# AVR-BASE.net
KiCad netlist of a schematic drawn in EAGLE
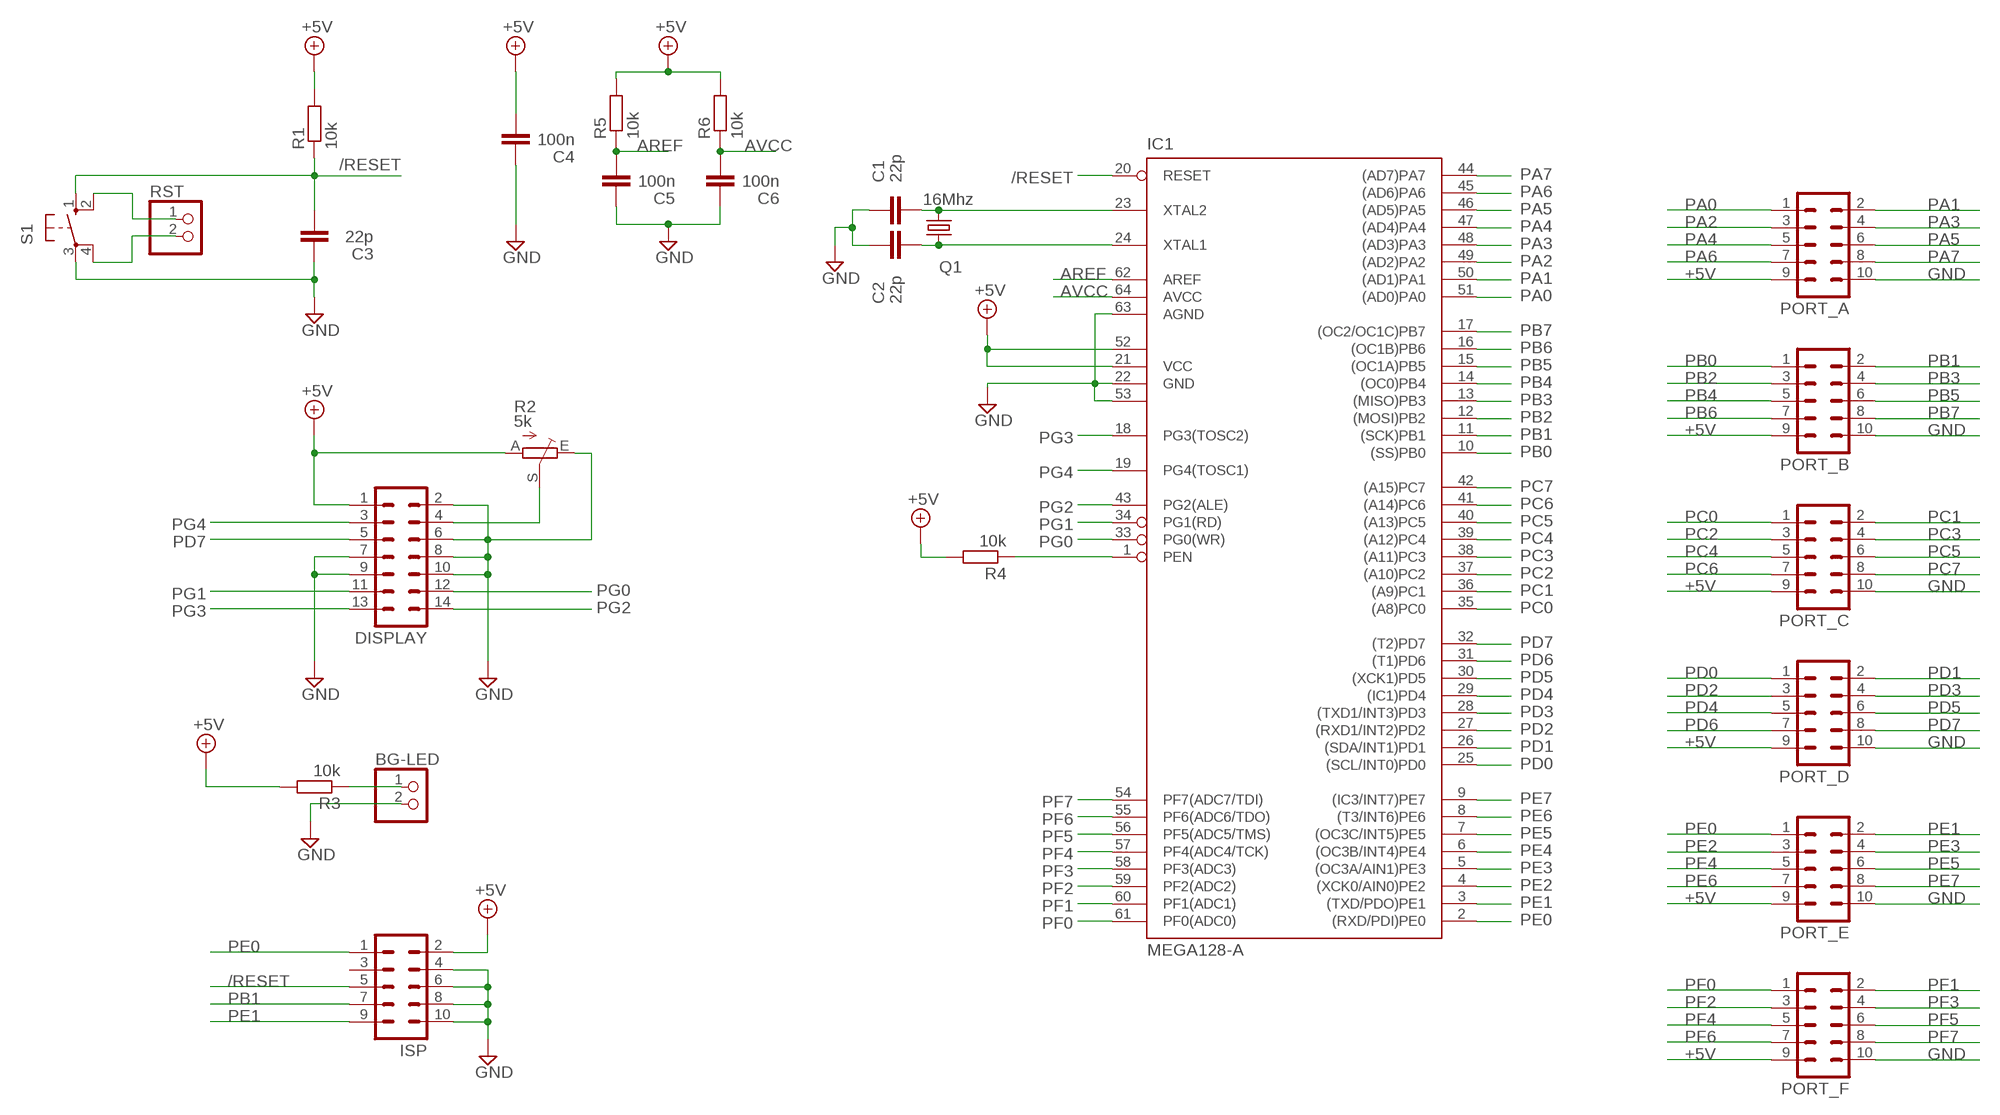
[diagram p0: schematic, sheet 1]
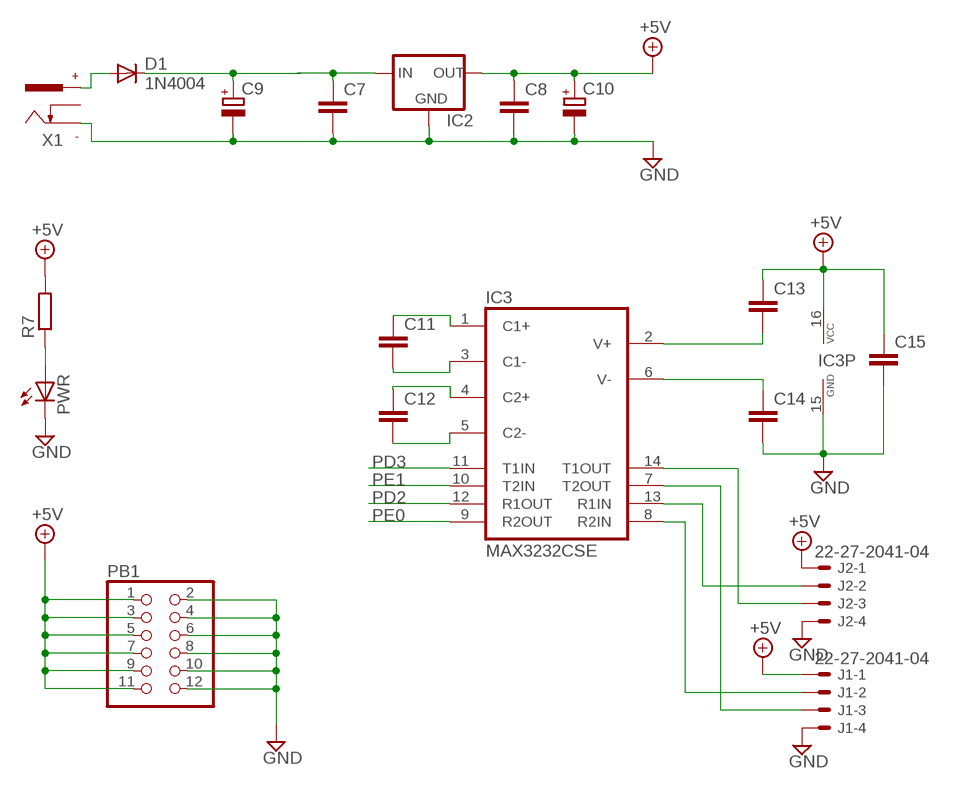
[diagram p1: schematic, sheet 2]

(export (version "E")
  (design (tool "Eeschema 10.0.6"))
  (components
    (comp (ref "C7")
      (value "C-EU025-025X050")
      (footprint "eagle-import:C025-025X050")
      (libsource (lib "eagle-import") (part "C-EU025-025X050"))
    )
    (comp (ref "C8")
      (value "C-EU025-025X050")
      (footprint "eagle-import:C025-025X050")
      (libsource (lib "eagle-import") (part "C-EU025-025X050"))
    )
    (comp (ref "C9")
      (value "CPOL-EUE3.5-8")
      (footprint "eagle-import:E3,5-8")
      (libsource (lib "eagle-import") (part "CPOL-EUE3.5-8"))
    )
    (comp (ref "C10")
      (value "CPOL-EUE3.5-8")
      (footprint "eagle-import:E3,5-8")
      (libsource (lib "eagle-import") (part "CPOL-EUE3.5-8"))
    )
    (comp (ref "C11")
      (value "C-EU025-025X050")
      (footprint "eagle-import:C025-025X050")
      (libsource (lib "eagle-import") (part "C-EU025-025X050"))
    )
    (comp (ref "C12")
      (value "C-EU025-025X050")
      (footprint "eagle-import:C025-025X050")
      (libsource (lib "eagle-import") (part "C-EU025-025X050"))
    )
    (comp (ref "C13")
      (value "C-EU025-025X050")
      (footprint "eagle-import:C025-025X050")
      (libsource (lib "eagle-import") (part "C-EU025-025X050"))
    )
    (comp (ref "C14")
      (value "C-EU025-025X050")
      (footprint "eagle-import:C025-025X050")
      (libsource (lib "eagle-import") (part "C-EU025-025X050"))
    )
    (comp (ref "C15")
      (value "C-EU025-025X050")
      (footprint "eagle-import:C025-025X050")
      (libsource (lib "eagle-import") (part "C-EU025-025X050"))
    )
    (comp (ref "D1")
      (value "1N4004")
      (footprint "eagle-import:DO41-10")
      (libsource (lib "eagle-import") (part "1N4004"))
    )
    (comp (ref "IC2")
      (value "78XXL")
      (footprint "eagle-import:78XXL")
      (libsource (lib "eagle-import") (part "78XXL"))
    )
    (comp (ref "IC3")
      (value "MAX3232CSE")
      (footprint "eagle-import:SO16")
      (libsource (lib "eagle-import") (part "MAX3232SEC"))
    )
    (comp (ref "J1")
      (value "22-27-2041-04")
      (footprint "eagle-import:6410-04")
      (libsource (lib "eagle-import") (part "22-?-0427-2041"))
    )
    (comp (ref "J2")
      (value "22-27-2041-04")
      (footprint "eagle-import:6410-04")
      (libsource (lib "eagle-import") (part "22-?-0427-2041"))
    )
    (comp (ref "PB1")
      (value "PINHD-2X6")
      (footprint "eagle-import:2X06")
      (libsource (lib "eagle-import") (part "PINHD-2X6"))
    )
    (comp (ref "PWR")
      (value "LED3MM")
      (footprint "eagle-import:LED3MM")
      (libsource (lib "eagle-import") (part "LED3MM"))
    )
    (comp (ref "R7")
      (value "R-EU_0204/5")
      (footprint "eagle-import:0204_5")
      (libsource (lib "eagle-import") (part "R-EU_0204/5"))
    )
    (comp (ref "X1")
      (value "737992-55")
      (footprint "eagle-import:737992-5")
      (libsource (lib "eagle-import") (part "737992-55"))
    )
    (comp (ref "BG-LED")
      (value "PINHD-1X2")
      (footprint "eagle-import:1X02")
      (libsource (lib "eagle-import") (part "PINHD-1X2"))
    )
    (comp (ref "C1")
      (value "22p")
      (footprint "eagle-import:C025-025X050")
      (libsource (lib "eagle-import") (part "C-EU025-025X050"))
    )
    (comp (ref "C2")
      (value "22p")
      (footprint "eagle-import:C025-025X050")
      (libsource (lib "eagle-import") (part "C-EU025-025X050"))
    )
    (comp (ref "C3")
      (value "22p")
      (footprint "eagle-import:C025-025X050")
      (libsource (lib "eagle-import") (part "C-EU025-025X050"))
    )
    (comp (ref "C4")
      (value "100n")
      (footprint "eagle-import:C025-025X050")
      (libsource (lib "eagle-import") (part "C-EU025-025X050"))
    )
    (comp (ref "C5")
      (value "100n")
      (footprint "eagle-import:C025-025X050")
      (libsource (lib "eagle-import") (part "C-EU025-025X050"))
    )
    (comp (ref "C6")
      (value "100n")
      (footprint "eagle-import:C025-025X050")
      (libsource (lib "eagle-import") (part "C-EU025-025X050"))
    )
    (comp (ref "DISPLAY")
      (value "ML14")
      (footprint "eagle-import:ML14")
      (libsource (lib "eagle-import") (part "ML14"))
    )
    (comp (ref "IC1")
      (value "MEGA128-A")
      (footprint "eagle-import:TQFP64")
      (libsource (lib "eagle-import") (part "MEGA128-A"))
    )
    (comp (ref "ISP")
      (value "ML10")
      (footprint "eagle-import:ML10")
      (libsource (lib "eagle-import") (part "ML10"))
    )
    (comp (ref "PORT_A")
      (value "ML10")
      (footprint "eagle-import:ML10")
      (libsource (lib "eagle-import") (part "ML10"))
    )
    (comp (ref "PORT_B")
      (value "ML10")
      (footprint "eagle-import:ML10")
      (libsource (lib "eagle-import") (part "ML10"))
    )
    (comp (ref "PORT_C")
      (value "ML10")
      (footprint "eagle-import:ML10")
      (libsource (lib "eagle-import") (part "ML10"))
    )
    (comp (ref "PORT_D")
      (value "ML10")
      (footprint "eagle-import:ML10")
      (libsource (lib "eagle-import") (part "ML10"))
    )
    (comp (ref "PORT_E")
      (value "ML10")
      (footprint "eagle-import:ML10")
      (libsource (lib "eagle-import") (part "ML10"))
    )
    (comp (ref "PORT_F")
      (value "ML10")
      (footprint "eagle-import:ML10")
      (libsource (lib "eagle-import") (part "ML10"))
    )
    (comp (ref "Q1")
      (value "16Mhz")
      (footprint "eagle-import:HC49U-V")
      (libsource (lib "eagle-import") (part "CRYSTALHC49U-V"))
    )
    (comp (ref "R1")
      (value "10k")
      (footprint "eagle-import:0207_7")
      (libsource (lib "eagle-import") (part "R-EU_0207/7"))
    )
    (comp (ref "R2")
      (value "5k")
      (footprint "eagle-import:B25P")
      (libsource (lib "eagle-import") (part "TRIM_EU-B25P"))
    )
    (comp (ref "R3")
      (value "10k")
      (footprint "eagle-import:0207_7")
      (libsource (lib "eagle-import") (part "R-EU_0207/7"))
    )
    (comp (ref "R4")
      (value "10k")
      (footprint "eagle-import:0204_5")
      (libsource (lib "eagle-import") (part "R-EU_0204/5"))
    )
    (comp (ref "R5")
      (value "10k")
      (footprint "eagle-import:0204_5")
      (libsource (lib "eagle-import") (part "R-EU_0204/5"))
    )
    (comp (ref "R6")
      (value "10k")
      (footprint "eagle-import:0204_5")
      (libsource (lib "eagle-import") (part "R-EU_0204/5"))
    )
    (comp (ref "RST")
      (value "PINHD-1X2")
      (footprint "eagle-import:1X02")
      (libsource (lib "eagle-import") (part "PINHD-1X2"))
    )
    (comp (ref "S1")
      (value "10-XX")
      (footprint "eagle-import:B3F-10XX")
      (libsource (lib "eagle-import") (part "10-XX"))
    )
  )
  (nets
    (net (code "1") (name "+5V") (class "Default")
      (node (ref "C10") (pin "+") (pinfunction "+_+") (pintype "passive"))
      (node (ref "C13") (pin "1") (pinfunction "1_1") (pintype "passive"))
      (node (ref "C15") (pin "1") (pinfunction "1_1") (pintype "passive"))
      (node (ref "C4") (pin "2") (pinfunction "2_2") (pintype "passive"))
      (node (ref "C8") (pin "1") (pinfunction "1_1") (pintype "passive"))
      (node (ref "DISPLAY") (pin "1") (pinfunction "1_1") (pintype "passive"))
      (node (ref "IC1") (pin "21") (pinfunction "VCC_21") (pintype "power_in"))
      (node (ref "IC1") (pin "52") (pinfunction "VCC1_52") (pintype "power_in"))
      (node (ref "IC2") (pin "OUT") (pinfunction "OUT_OUT") (pintype "passive"))
      (node (ref "IC3") (pin "16") (pinfunction "VCC_16") (pintype "power_in"))
      (node (ref "ISP") (pin "2") (pinfunction "2_2") (pintype "passive"))
      (node (ref "J1") (pin "1") (pinfunction "S_1") (pintype "passive"))
      (node (ref "J2") (pin "1") (pinfunction "S_1") (pintype "passive"))
      (node (ref "PB1") (pin "1") (pinfunction "1_1") (pintype "passive"))
      (node (ref "PB1") (pin "11") (pinfunction "11_11") (pintype "passive"))
      (node (ref "PB1") (pin "3") (pinfunction "3_3") (pintype "passive"))
      (node (ref "PB1") (pin "5") (pinfunction "5_5") (pintype "passive"))
      (node (ref "PB1") (pin "7") (pinfunction "7_7") (pintype "passive"))
      (node (ref "PB1") (pin "9") (pinfunction "9_9") (pintype "passive"))
      (node (ref "PORT_A") (pin "9") (pinfunction "9_9") (pintype "passive"))
      (node (ref "PORT_B") (pin "9") (pinfunction "9_9") (pintype "passive"))
      (node (ref "PORT_C") (pin "9") (pinfunction "9_9") (pintype "passive"))
      (node (ref "PORT_D") (pin "9") (pinfunction "9_9") (pintype "passive"))
      (node (ref "PORT_E") (pin "9") (pinfunction "9_9") (pintype "passive"))
      (node (ref "PORT_F") (pin "9") (pinfunction "9_9") (pintype "passive"))
      (node (ref "R1") (pin "2") (pinfunction "2_2") (pintype "passive"))
      (node (ref "R2") (pin "A") (pinfunction "A_A") (pintype "passive"))
      (node (ref "R3") (pin "2") (pinfunction "2_2") (pintype "passive"))
      (node (ref "R4") (pin "2") (pinfunction "2_2") (pintype "passive"))
      (node (ref "R5") (pin "2") (pinfunction "2_2") (pintype "passive"))
      (node (ref "R6") (pin "2") (pinfunction "2_2") (pintype "passive"))
      (node (ref "R7") (pin "2") (pinfunction "2_2") (pintype "passive"))
    )
    (net (code "2") (name "AREF") (class "Default")
      (node (ref "C5") (pin "2") (pinfunction "2_2") (pintype "passive"))
      (node (ref "IC1") (pin "62") (pinfunction "AREF_62") (pintype "bidirectional"))
      (node (ref "R5") (pin "1") (pinfunction "1_1") (pintype "passive"))
    )
    (net (code "3") (name "AVCC") (class "Default")
      (node (ref "C6") (pin "2") (pinfunction "2_2") (pintype "passive"))
      (node (ref "IC1") (pin "64") (pinfunction "AVCC_64") (pintype "bidirectional"))
      (node (ref "R6") (pin "1") (pinfunction "1_1") (pintype "passive"))
    )
    (net (code "4") (name "GND") (class "Default")
      (node (ref "BG-LED") (pin "2") (pinfunction "2_2") (pintype "passive"))
      (node (ref "C1") (pin "1") (pinfunction "1_1") (pintype "passive"))
      (node (ref "C10") (pin "-") (pinfunction "-_-") (pintype "passive"))
      (node (ref "C14") (pin "2") (pinfunction "2_2") (pintype "passive"))
      (node (ref "C15") (pin "2") (pinfunction "2_2") (pintype "passive"))
      (node (ref "C2") (pin "1") (pinfunction "1_1") (pintype "passive"))
      (node (ref "C3") (pin "1") (pinfunction "1_1") (pintype "passive"))
      (node (ref "C4") (pin "1") (pinfunction "1_1") (pintype "passive"))
      (node (ref "C5") (pin "1") (pinfunction "1_1") (pintype "passive"))
      (node (ref "C6") (pin "1") (pinfunction "1_1") (pintype "passive"))
      (node (ref "C7") (pin "2") (pinfunction "2_2") (pintype "passive"))
      (node (ref "C8") (pin "2") (pinfunction "2_2") (pintype "passive"))
      (node (ref "C9") (pin "-") (pinfunction "-_-") (pintype "passive"))
      (node (ref "DISPLAY") (pin "10") (pinfunction "10_10") (pintype "passive"))
      (node (ref "DISPLAY") (pin "2") (pinfunction "2_2") (pintype "passive"))
      (node (ref "DISPLAY") (pin "6") (pinfunction "6_6") (pintype "passive"))
      (node (ref "DISPLAY") (pin "7") (pinfunction "7_7") (pintype "passive"))
      (node (ref "DISPLAY") (pin "8") (pinfunction "8_8") (pintype "passive"))
      (node (ref "DISPLAY") (pin "9") (pinfunction "9_9") (pintype "passive"))
      (node (ref "IC1") (pin "22") (pinfunction "GND_22") (pintype "power_in"))
      (node (ref "IC1") (pin "53") (pinfunction "GND1_53") (pintype "power_in"))
      (node (ref "IC1") (pin "63") (pinfunction "AGND_63") (pintype "bidirectional"))
      (node (ref "IC2") (pin "GND") (pinfunction "GND_GND") (pintype "input"))
      (node (ref "IC3") (pin "15") (pinfunction "GND_15") (pintype "power_in"))
      (node (ref "ISP") (pin "10") (pinfunction "10_10") (pintype "passive"))
      (node (ref "ISP") (pin "4") (pinfunction "4_4") (pintype "passive"))
      (node (ref "ISP") (pin "6") (pinfunction "6_6") (pintype "passive"))
      (node (ref "ISP") (pin "8") (pinfunction "8_8") (pintype "passive"))
      (node (ref "J1") (pin "4") (pinfunction "S_4") (pintype "passive"))
      (node (ref "J2") (pin "4") (pinfunction "S_4") (pintype "passive"))
      (node (ref "PB1") (pin "10") (pinfunction "10_10") (pintype "passive"))
      (node (ref "PB1") (pin "12") (pinfunction "12_12") (pintype "passive"))
      (node (ref "PB1") (pin "2") (pinfunction "2_2") (pintype "passive"))
      (node (ref "PB1") (pin "4") (pinfunction "4_4") (pintype "passive"))
      (node (ref "PB1") (pin "6") (pinfunction "6_6") (pintype "passive"))
      (node (ref "PB1") (pin "8") (pinfunction "8_8") (pintype "passive"))
      (node (ref "PORT_A") (pin "10") (pinfunction "10_10") (pintype "passive"))
      (node (ref "PORT_B") (pin "10") (pinfunction "10_10") (pintype "passive"))
      (node (ref "PORT_C") (pin "10") (pinfunction "10_10") (pintype "passive"))
      (node (ref "PORT_D") (pin "10") (pinfunction "10_10") (pintype "passive"))
      (node (ref "PORT_E") (pin "10") (pinfunction "10_10") (pintype "passive"))
      (node (ref "PORT_F") (pin "10") (pinfunction "10_10") (pintype "passive"))
      (node (ref "PWR") (pin "K") (pinfunction "C_K") (pintype "passive"))
      (node (ref "R2") (pin "E") (pinfunction "E_E") (pintype "passive"))
      (node (ref "S1") (pin "3") (pinfunction "P_3") (pintype "passive"))
      (node (ref "X1") (pin "+") (pinfunction "+_+") (pintype "passive"))
    )
    (net (code "5") (name "Net-(BG-LED-Pad1)") (class "Default")
      (node (ref "BG-LED") (pin "1") (pinfunction "1_1") (pintype "passive"))
      (node (ref "R3") (pin "1") (pinfunction "1_1") (pintype "passive"))
    )
    (net (code "6") (name "Net-(C7-Pad1)") (class "Default")
      (node (ref "C7") (pin "1") (pinfunction "1_1") (pintype "passive"))
      (node (ref "C9") (pin "+") (pinfunction "+_+") (pintype "passive"))
      (node (ref "D1") (pin "C") (pinfunction "C_C") (pintype "passive"))
      (node (ref "IC2") (pin "IN") (pinfunction "IN_IN") (pintype "input"))
    )
    (net (code "7") (name "Net-(D1-PadA)") (class "Default")
      (node (ref "D1") (pin "A") (pinfunction "A_A") (pintype "passive"))
      (node (ref "X1") (pin "-1") (pinfunction "-1_-1") (pintype "passive"))
    )
    (net (code "8") (name "Net-(DISPLAY-Pad4)") (class "Default")
      (node (ref "DISPLAY") (pin "4") (pinfunction "4_4") (pintype "passive"))
      (node (ref "R2") (pin "S") (pinfunction "S_S") (pintype "passive"))
    )
    (net (code "9") (name "Net-(IC1-PEN)") (class "Default")
      (node (ref "IC1") (pin "1") (pinfunction "PEN_1") (pintype "input"))
      (node (ref "R4") (pin "1") (pinfunction "1_1") (pintype "passive"))
    )
    (net (code "10") (name "Net-(IC1-XTAL1)") (class "Default")
      (node (ref "C2") (pin "2") (pinfunction "2_2") (pintype "passive"))
      (node (ref "IC1") (pin "24") (pinfunction "XTAL1_24") (pintype "bidirectional"))
      (node (ref "Q1") (pin "1") (pinfunction "1_1") (pintype "passive"))
    )
    (net (code "11") (name "Net-(IC1-XTAL2)") (class "Default")
      (node (ref "C1") (pin "2") (pinfunction "2_2") (pintype "passive"))
      (node (ref "IC1") (pin "23") (pinfunction "XTAL2_23") (pintype "bidirectional"))
      (node (ref "Q1") (pin "2") (pinfunction "2_2") (pintype "passive"))
    )
    (net (code "12") (name "Net-(IC3A-C1+)") (class "Default")
      (node (ref "C11") (pin "1") (pinfunction "1_1") (pintype "passive"))
      (node (ref "IC3") (pin "1") (pinfunction "C1+_1") (pintype "bidirectional"))
    )
    (net (code "13") (name "Net-(IC3A-C1-)") (class "Default")
      (node (ref "C11") (pin "2") (pinfunction "2_2") (pintype "passive"))
      (node (ref "IC3") (pin "3") (pinfunction "C1-_3") (pintype "bidirectional"))
    )
    (net (code "14") (name "Net-(IC3A-C2+)") (class "Default")
      (node (ref "C12") (pin "1") (pinfunction "1_1") (pintype "passive"))
      (node (ref "IC3") (pin "4") (pinfunction "C2+_4") (pintype "bidirectional"))
    )
    (net (code "15") (name "Net-(IC3A-C2-)") (class "Default")
      (node (ref "C12") (pin "2") (pinfunction "2_2") (pintype "passive"))
      (node (ref "IC3") (pin "5") (pinfunction "C2-_5") (pintype "bidirectional"))
    )
    (net (code "16") (name "Net-(IC3A-R1IN)") (class "Default")
      (node (ref "IC3") (pin "13") (pinfunction "R1IN_13") (pintype "input"))
      (node (ref "J2") (pin "2") (pinfunction "S_2") (pintype "passive"))
    )
    (net (code "17") (name "Net-(IC3A-R2IN)") (class "Default")
      (node (ref "IC3") (pin "8") (pinfunction "R2IN_8") (pintype "input"))
      (node (ref "J1") (pin "2") (pinfunction "S_2") (pintype "passive"))
    )
    (net (code "18") (name "Net-(IC3A-T1OUT)") (class "Default")
      (node (ref "IC3") (pin "14") (pinfunction "T1OUT_14") (pintype "output"))
      (node (ref "J2") (pin "3") (pinfunction "S_3") (pintype "passive"))
    )
    (net (code "19") (name "Net-(IC3A-T2OUT)") (class "Default")
      (node (ref "IC3") (pin "7") (pinfunction "T2OUT_7") (pintype "output"))
      (node (ref "J1") (pin "3") (pinfunction "S_3") (pintype "passive"))
    )
    (net (code "20") (name "Net-(IC3A-V+)") (class "Default")
      (node (ref "C13") (pin "2") (pinfunction "2_2") (pintype "passive"))
      (node (ref "IC3") (pin "2") (pinfunction "V+_2") (pintype "bidirectional"))
    )
    (net (code "21") (name "Net-(IC3A-V-)") (class "Default")
      (node (ref "C14") (pin "1") (pinfunction "1_1") (pintype "passive"))
      (node (ref "IC3") (pin "6") (pinfunction "V-_6") (pintype "bidirectional"))
    )
    (net (code "22") (name "Net-(PWR-PadA)") (class "Default")
      (node (ref "PWR") (pin "A") (pinfunction "A_A") (pintype "passive"))
      (node (ref "R7") (pin "1") (pinfunction "1_1") (pintype "passive"))
    )
    (net (code "23") (name "Net-(S1-P1)") (class "Default")
      (node (ref "RST") (pin "2") (pinfunction "2_2") (pintype "passive"))
      (node (ref "S1") (pin "4") (pinfunction "P1_4") (pintype "passive"))
    )
    (net (code "24") (name "Net-(S1-S1)") (class "Default")
      (node (ref "RST") (pin "1") (pinfunction "1_1") (pintype "passive"))
      (node (ref "S1") (pin "2") (pinfunction "S1_2") (pintype "passive"))
    )
    (net (code "25") (name "PA0") (class "Default")
      (node (ref "IC1") (pin "51") (pinfunction "(AD0)PA0_51") (pintype "bidirectional"))
      (node (ref "PORT_A") (pin "1") (pinfunction "1_1") (pintype "passive"))
    )
    (net (code "26") (name "PA1") (class "Default")
      (node (ref "IC1") (pin "50") (pinfunction "(AD1)PA1_50") (pintype "bidirectional"))
      (node (ref "PORT_A") (pin "2") (pinfunction "2_2") (pintype "passive"))
    )
    (net (code "27") (name "PA2") (class "Default")
      (node (ref "IC1") (pin "49") (pinfunction "(AD2)PA2_49") (pintype "bidirectional"))
      (node (ref "PORT_A") (pin "3") (pinfunction "3_3") (pintype "passive"))
    )
    (net (code "28") (name "PA3") (class "Default")
      (node (ref "IC1") (pin "48") (pinfunction "(AD3)PA3_48") (pintype "bidirectional"))
      (node (ref "PORT_A") (pin "4") (pinfunction "4_4") (pintype "passive"))
    )
    (net (code "29") (name "PA4") (class "Default")
      (node (ref "IC1") (pin "47") (pinfunction "(AD4)PA4_47") (pintype "bidirectional"))
      (node (ref "PORT_A") (pin "5") (pinfunction "5_5") (pintype "passive"))
    )
    (net (code "30") (name "PA5") (class "Default")
      (node (ref "IC1") (pin "46") (pinfunction "(AD5)PA5_46") (pintype "bidirectional"))
      (node (ref "PORT_A") (pin "6") (pinfunction "6_6") (pintype "passive"))
    )
    (net (code "31") (name "PA6") (class "Default")
      (node (ref "IC1") (pin "45") (pinfunction "(AD6)PA6_45") (pintype "bidirectional"))
      (node (ref "PORT_A") (pin "7") (pinfunction "7_7") (pintype "passive"))
    )
    (net (code "32") (name "PA7") (class "Default")
      (node (ref "IC1") (pin "44") (pinfunction "(AD7)PA7_44") (pintype "bidirectional"))
      (node (ref "PORT_A") (pin "8") (pinfunction "8_8") (pintype "passive"))
    )
    (net (code "33") (name "PB0") (class "Default")
      (node (ref "IC1") (pin "10") (pinfunction "(SS)PB0_10") (pintype "bidirectional"))
      (node (ref "PORT_B") (pin "1") (pinfunction "1_1") (pintype "passive"))
    )
    (net (code "34") (name "PB1") (class "Default")
      (node (ref "IC1") (pin "11") (pinfunction "(SCK)PB1_11") (pintype "bidirectional"))
      (node (ref "ISP") (pin "7") (pinfunction "7_7") (pintype "passive"))
      (node (ref "PORT_B") (pin "2") (pinfunction "2_2") (pintype "passive"))
    )
    (net (code "35") (name "PB2") (class "Default")
      (node (ref "IC1") (pin "12") (pinfunction "(MOSI)PB2_12") (pintype "bidirectional"))
      (node (ref "PORT_B") (pin "3") (pinfunction "3_3") (pintype "passive"))
    )
    (net (code "36") (name "PB3") (class "Default")
      (node (ref "IC1") (pin "13") (pinfunction "(MISO)PB3_13") (pintype "bidirectional"))
      (node (ref "PORT_B") (pin "4") (pinfunction "4_4") (pintype "passive"))
    )
    (net (code "37") (name "PB4") (class "Default")
      (node (ref "IC1") (pin "14") (pinfunction "(OC0)PB4_14") (pintype "bidirectional"))
      (node (ref "PORT_B") (pin "5") (pinfunction "5_5") (pintype "passive"))
    )
    (net (code "38") (name "PB5") (class "Default")
      (node (ref "IC1") (pin "15") (pinfunction "(OC1A)PB5_15") (pintype "bidirectional"))
      (node (ref "PORT_B") (pin "6") (pinfunction "6_6") (pintype "passive"))
    )
    (net (code "39") (name "PB6") (class "Default")
      (node (ref "IC1") (pin "16") (pinfunction "(OC1B)PB6_16") (pintype "bidirectional"))
      (node (ref "PORT_B") (pin "7") (pinfunction "7_7") (pintype "passive"))
    )
    (net (code "40") (name "PB7") (class "Default")
      (node (ref "IC1") (pin "17") (pinfunction "(OC2/OC1C)PB7_17") (pintype "bidirectional"))
      (node (ref "PORT_B") (pin "8") (pinfunction "8_8") (pintype "passive"))
    )
    (net (code "41") (name "PC0") (class "Default")
      (node (ref "IC1") (pin "35") (pinfunction "(A8)PC0_35") (pintype "output"))
      (node (ref "PORT_C") (pin "1") (pinfunction "1_1") (pintype "passive"))
    )
    (net (code "42") (name "PC1") (class "Default")
      (node (ref "IC1") (pin "36") (pinfunction "(A9)PC1_36") (pintype "output"))
      (node (ref "PORT_C") (pin "2") (pinfunction "2_2") (pintype "passive"))
    )
    (net (code "43") (name "PC2") (class "Default")
      (node (ref "IC1") (pin "37") (pinfunction "(A10)PC2_37") (pintype "output"))
      (node (ref "PORT_C") (pin "3") (pinfunction "3_3") (pintype "passive"))
    )
    (net (code "44") (name "PC3") (class "Default")
      (node (ref "IC1") (pin "38") (pinfunction "(A11)PC3_38") (pintype "output"))
      (node (ref "PORT_C") (pin "4") (pinfunction "4_4") (pintype "passive"))
    )
    (net (code "45") (name "PC4") (class "Default")
      (node (ref "IC1") (pin "39") (pinfunction "(A12)PC4_39") (pintype "output"))
      (node (ref "PORT_C") (pin "5") (pinfunction "5_5") (pintype "passive"))
    )
    (net (code "46") (name "PC5") (class "Default")
      (node (ref "IC1") (pin "40") (pinfunction "(A13)PC5_40") (pintype "output"))
      (node (ref "PORT_C") (pin "6") (pinfunction "6_6") (pintype "passive"))
    )
    (net (code "47") (name "PC6") (class "Default")
      (node (ref "IC1") (pin "41") (pinfunction "(A14)PC6_41") (pintype "output"))
      (node (ref "PORT_C") (pin "7") (pinfunction "7_7") (pintype "passive"))
    )
    (net (code "48") (name "PC7") (class "Default")
      (node (ref "IC1") (pin "42") (pinfunction "(A15)PC7_42") (pintype "output"))
      (node (ref "PORT_C") (pin "8") (pinfunction "8_8") (pintype "passive"))
    )
    (net (code "49") (name "PD0") (class "Default")
      (node (ref "IC1") (pin "25") (pinfunction "(SCL/INT0)PD0_25") (pintype "bidirectional"))
      (node (ref "PORT_D") (pin "1") (pinfunction "1_1") (pintype "passive"))
    )
    (net (code "50") (name "PD1") (class "Default")
      (node (ref "IC1") (pin "26") (pinfunction "(SDA/INT1)PD1_26") (pintype "bidirectional"))
      (node (ref "PORT_D") (pin "2") (pinfunction "2_2") (pintype "passive"))
    )
    (net (code "51") (name "PD2") (class "Default")
      (node (ref "IC1") (pin "27") (pinfunction "(RXD1/INT2)PD2_27") (pintype "bidirectional"))
      (node (ref "IC3") (pin "12") (pinfunction "R1OUT_12") (pintype "output"))
      (node (ref "PORT_D") (pin "3") (pinfunction "3_3") (pintype "passive"))
    )
    (net (code "52") (name "PD3") (class "Default")
      (node (ref "IC1") (pin "28") (pinfunction "(TXD1/INT3)PD3_28") (pintype "bidirectional"))
      (node (ref "IC3") (pin "11") (pinfunction "T1IN_11") (pintype "input"))
      (node (ref "PORT_D") (pin "4") (pinfunction "4_4") (pintype "passive"))
    )
    (net (code "53") (name "PD4") (class "Default")
      (node (ref "IC1") (pin "29") (pinfunction "(IC1)PD4_29") (pintype "bidirectional"))
      (node (ref "PORT_D") (pin "5") (pinfunction "5_5") (pintype "passive"))
    )
    (net (code "54") (name "PD5") (class "Default")
      (node (ref "IC1") (pin "30") (pinfunction "(XCK1)PD5_30") (pintype "bidirectional"))
      (node (ref "PORT_D") (pin "6") (pinfunction "6_6") (pintype "passive"))
    )
    (net (code "55") (name "PD6") (class "Default")
      (node (ref "IC1") (pin "31") (pinfunction "(T1)PD6_31") (pintype "bidirectional"))
      (node (ref "PORT_D") (pin "7") (pinfunction "7_7") (pintype "passive"))
    )
    (net (code "56") (name "PD7") (class "Default")
      (node (ref "DISPLAY") (pin "5") (pinfunction "5_5") (pintype "passive"))
      (node (ref "IC1") (pin "32") (pinfunction "(T2)PD7_32") (pintype "bidirectional"))
      (node (ref "PORT_D") (pin "8") (pinfunction "8_8") (pintype "passive"))
    )
    (net (code "57") (name "PE0") (class "Default")
      (node (ref "IC1") (pin "2") (pinfunction "(RXD/PDI)PE0_2") (pintype "bidirectional"))
      (node (ref "IC3") (pin "9") (pinfunction "R2OUT_9") (pintype "output"))
      (node (ref "ISP") (pin "1") (pinfunction "1_1") (pintype "passive"))
      (node (ref "PORT_E") (pin "1") (pinfunction "1_1") (pintype "passive"))
    )
    (net (code "58") (name "PE1") (class "Default")
      (node (ref "IC1") (pin "3") (pinfunction "(TXD/PDO)PE1_3") (pintype "bidirectional"))
      (node (ref "IC3") (pin "10") (pinfunction "T2IN_10") (pintype "input"))
      (node (ref "ISP") (pin "9") (pinfunction "9_9") (pintype "passive"))
      (node (ref "PORT_E") (pin "2") (pinfunction "2_2") (pintype "passive"))
    )
    (net (code "59") (name "PE2") (class "Default")
      (node (ref "IC1") (pin "4") (pinfunction "(XCK0/AIN0)PE2_4") (pintype "bidirectional"))
      (node (ref "PORT_E") (pin "3") (pinfunction "3_3") (pintype "passive"))
    )
    (net (code "60") (name "PE3") (class "Default")
      (node (ref "IC1") (pin "5") (pinfunction "(OC3A/AIN1)PE3_5") (pintype "bidirectional"))
      (node (ref "PORT_E") (pin "4") (pinfunction "4_4") (pintype "passive"))
    )
    (net (code "61") (name "PE4") (class "Default")
      (node (ref "IC1") (pin "6") (pinfunction "(OC3B/INT4)PE4_6") (pintype "bidirectional"))
      (node (ref "PORT_E") (pin "5") (pinfunction "5_5") (pintype "passive"))
    )
    (net (code "62") (name "PE5") (class "Default")
      (node (ref "IC1") (pin "7") (pinfunction "(OC3C/INT5)PE5_7") (pintype "bidirectional"))
      (node (ref "PORT_E") (pin "6") (pinfunction "6_6") (pintype "passive"))
    )
    (net (code "63") (name "PE6") (class "Default")
      (node (ref "IC1") (pin "8") (pinfunction "(T3/INT6)PE6_8") (pintype "bidirectional"))
      (node (ref "PORT_E") (pin "7") (pinfunction "7_7") (pintype "passive"))
    )
    (net (code "64") (name "PE7") (class "Default")
      (node (ref "IC1") (pin "9") (pinfunction "(IC3/INT7)PE7_9") (pintype "bidirectional"))
      (node (ref "PORT_E") (pin "8") (pinfunction "8_8") (pintype "passive"))
    )
    (net (code "65") (name "PF0") (class "Default")
      (node (ref "IC1") (pin "61") (pinfunction "PF0(ADC0)_61") (pintype "input"))
      (node (ref "PORT_F") (pin "1") (pinfunction "1_1") (pintype "passive"))
    )
    (net (code "66") (name "PF1") (class "Default")
      (node (ref "IC1") (pin "60") (pinfunction "PF1(ADC1)_60") (pintype "input"))
      (node (ref "PORT_F") (pin "2") (pinfunction "2_2") (pintype "passive"))
    )
    (net (code "67") (name "PF2") (class "Default")
      (node (ref "IC1") (pin "59") (pinfunction "PF2(ADC2)_59") (pintype "input"))
      (node (ref "PORT_F") (pin "3") (pinfunction "3_3") (pintype "passive"))
    )
    (net (code "68") (name "PF3") (class "Default")
      (node (ref "IC1") (pin "58") (pinfunction "PF3(ADC3)_58") (pintype "input"))
      (node (ref "PORT_F") (pin "4") (pinfunction "4_4") (pintype "passive"))
    )
    (net (code "69") (name "PF4") (class "Default")
      (node (ref "IC1") (pin "57") (pinfunction "PF4(ADC4/TCK)_57") (pintype "input"))
      (node (ref "PORT_F") (pin "5") (pinfunction "5_5") (pintype "passive"))
    )
    (net (code "70") (name "PF5") (class "Default")
      (node (ref "IC1") (pin "56") (pinfunction "PF5(ADC5/TMS)_56") (pintype "input"))
      (node (ref "PORT_F") (pin "6") (pinfunction "6_6") (pintype "passive"))
    )
    (net (code "71") (name "PF6") (class "Default")
      (node (ref "IC1") (pin "55") (pinfunction "PF6(ADC6/TDO)_55") (pintype "input"))
      (node (ref "PORT_F") (pin "7") (pinfunction "7_7") (pintype "passive"))
    )
    (net (code "72") (name "PF7") (class "Default")
      (node (ref "IC1") (pin "54") (pinfunction "PF7(ADC7/TDI)_54") (pintype "input"))
      (node (ref "PORT_F") (pin "8") (pinfunction "8_8") (pintype "passive"))
    )
    (net (code "73") (name "PG0") (class "Default")
      (node (ref "DISPLAY") (pin "12") (pinfunction "12_12") (pintype "passive"))
      (node (ref "IC1") (pin "33") (pinfunction "PG0(WR)_33") (pintype "bidirectional"))
    )
    (net (code "74") (name "PG1") (class "Default")
      (node (ref "DISPLAY") (pin "11") (pinfunction "11_11") (pintype "passive"))
      (node (ref "IC1") (pin "34") (pinfunction "PG1(RD)_34") (pintype "bidirectional"))
    )
    (net (code "75") (name "PG2") (class "Default")
      (node (ref "DISPLAY") (pin "14") (pinfunction "14_14") (pintype "passive"))
      (node (ref "IC1") (pin "43") (pinfunction "PG2(ALE)_43") (pintype "bidirectional"))
    )
    (net (code "76") (name "PG3") (class "Default")
      (node (ref "DISPLAY") (pin "13") (pinfunction "13_13") (pintype "passive"))
      (node (ref "IC1") (pin "18") (pinfunction "PG3(TOSC2)_18") (pintype "bidirectional"))
    )
    (net (code "77") (name "PG4") (class "Default")
      (node (ref "DISPLAY") (pin "3") (pinfunction "3_3") (pintype "passive"))
      (node (ref "IC1") (pin "19") (pinfunction "PG4(TOSC1)_19") (pintype "bidirectional"))
    )
    (net (code "78") (name "unconnected-(ISP-Pad3)") (class "Default")
      (node (ref "ISP") (pin "3") (pinfunction "3_3") (pintype "passive"))
    )
    (net (code "79") (name "unconnected-(X1-Pad-2)") (class "Default")
      (node (ref "X1") (pin "-2") (pinfunction "-2_-2") (pintype "passive"))
    )
    (net (code "80") (name "unconnected-(X1-PadK)") (class "Default")
      (node (ref "X1") (pin "K") (pinfunction "K_K") (pintype "passive"))
    )
    (net (code "81") (name "{slash}RESET") (class "Default")
      (node (ref "C3") (pin "2") (pinfunction "2_2") (pintype "passive"))
      (node (ref "IC1") (pin "20") (pinfunction "RESET_20") (pintype "input"))
      (node (ref "ISP") (pin "5") (pinfunction "5_5") (pintype "passive"))
      (node (ref "R1") (pin "1") (pinfunction "1_1") (pintype "passive"))
      (node (ref "S1") (pin "1") (pinfunction "S_1") (pintype "passive"))
    )
  )
)
